# chickengate.net
KiCad netlist of a schematic drawn in EAGLE
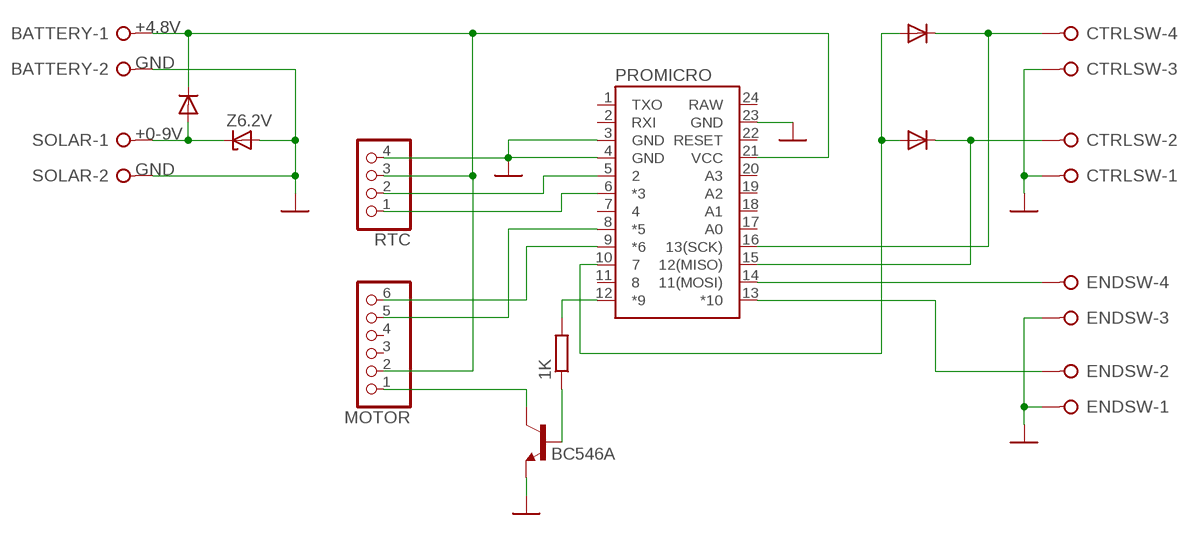
[diagram p0: schematic, sheet 1]

(export (version "E")
  (design (tool "Eeschema 10.0.6"))
  (components
    (comp (ref "1K")
      (value "R-EU_0207/12")
      (footprint "eagle-import:0207_12")
      (libsource (lib "eagle-import") (part "R-EU_0207/12"))
    )
    (comp (ref "BATTERY")
      (value "W237-02P")
      (footprint "eagle-import:W237-132")
      (libsource (lib "eagle-import") (part "W237-02P"))
    )
    (comp (ref "CTRLSW")
      (value "W237-04P")
      (footprint "eagle-import:W237-4P")
      (libsource (lib "eagle-import") (part "W237-04P"))
    )
    (comp (ref "D1")
      (value "1N4004")
      (footprint "eagle-import:DO41-10")
      (libsource (lib "eagle-import") (part "1N4004"))
    )
    (comp (ref "D2")
      (value "1N4004")
      (footprint "eagle-import:DO41-10")
      (libsource (lib "eagle-import") (part "1N4004"))
    )
    (comp (ref "D3")
      (value "1N4004")
      (footprint "eagle-import:DO41-10")
      (libsource (lib "eagle-import") (part "1N4004"))
    )
    (comp (ref "ENDSW")
      (value "W237-04P")
      (footprint "eagle-import:W237-4P")
      (libsource (lib "eagle-import") (part "W237-04P"))
    )
    (comp (ref "MOTOR")
      (value "PINHD-1X6")
      (footprint "eagle-import:1X06")
      (libsource (lib "eagle-import") (part "PINHD-1X6"))
    )
    (comp (ref "PROMICRO")
      (value "SPARKFUN_PRO_MICRO")
      (footprint "eagle-import:SPARKFUN_PRO_MICRO")
      (libsource (lib "eagle-import") (part "SPARKFUN_PRO_MICRO"))
    )
    (comp (ref "Q1")
      (value "BC546A")
      (footprint "eagle-import:TO92-EBC")
      (libsource (lib "eagle-import") (part "BC546A"))
    )
    (comp (ref "RTC")
      (value "PINHD-1X4")
      (footprint "eagle-import:1X04")
      (libsource (lib "eagle-import") (part "PINHD-1X4"))
    )
    (comp (ref "SOLAR")
      (value "W237-02P")
      (footprint "eagle-import:W237-132")
      (libsource (lib "eagle-import") (part "W237-02P"))
    )
    (comp (ref "Z6.2V")
      (value "ZPD")
      (footprint "eagle-import:DO35Z10")
      (libsource (lib "eagle-import") (part "ZPD"))
    )
  )
  (nets
    (net (code "1") (name "/+0-9V") (class "Default")
      (node (ref "D1") (pin "A") (pinfunction "A_A") (pintype "passive"))
      (node (ref "SOLAR") (pin "1") (pinfunction "KL_1") (pintype "passive"))
      (node (ref "Z6.2V") (pin "C") (pinfunction "C_C") (pintype "passive"))
    )
    (net (code "2") (name "/+4.8V") (class "Default")
      (node (ref "BATTERY") (pin "1") (pinfunction "KL_1") (pintype "passive"))
      (node (ref "D1") (pin "C") (pinfunction "C_C") (pintype "passive"))
      (node (ref "MOTOR") (pin "2") (pinfunction "2_2") (pintype "passive"))
      (node (ref "PROMICRO") (pin "21") (pinfunction "VCC_21") (pintype "power_in"))
      (node (ref "RTC") (pin "3") (pinfunction "3_3") (pintype "passive"))
    )
    (net (code "3") (name "/RAW") (class "Default")
      (node (ref "PROMICRO") (pin "24") (pinfunction "RAW_24") (pintype "power_in"))
    )
    (net (code "4") (name "GND") (class "Default")
      (node (ref "BATTERY") (pin "2") (pinfunction "KL_2") (pintype "passive"))
      (node (ref "CTRLSW") (pin "1") (pinfunction "KL_1") (pintype "passive"))
      (node (ref "CTRLSW") (pin "3") (pinfunction "KL_3") (pintype "passive"))
      (node (ref "ENDSW") (pin "1") (pinfunction "KL_1") (pintype "passive"))
      (node (ref "ENDSW") (pin "3") (pinfunction "KL_3") (pintype "passive"))
      (node (ref "PROMICRO") (pin "23") (pinfunction "GND_23") (pintype "power_in"))
      (node (ref "PROMICRO") (pin "3") (pinfunction "GND_3") (pintype "power_in"))
      (node (ref "PROMICRO") (pin "4") (pinfunction "GND_4") (pintype "power_in"))
      (node (ref "Q1") (pin "E") (pinfunction "E_E") (pintype "passive"))
      (node (ref "RTC") (pin "4") (pinfunction "4_4") (pintype "passive"))
      (node (ref "SOLAR") (pin "2") (pinfunction "KL_2") (pintype "passive"))
      (node (ref "Z6.2V") (pin "A") (pinfunction "A_A") (pintype "passive"))
    )
    (net (code "5") (name "Net-(1K-Pad1)") (class "Default")
      (node (ref "1K") (pin "1") (pinfunction "1_1") (pintype "passive"))
      (node (ref "Q1") (pin "B") (pinfunction "B_B") (pintype "passive"))
    )
    (net (code "6") (name "Net-(CTRLSWB-KL)") (class "Default")
      (node (ref "CTRLSW") (pin "2") (pinfunction "KL_2") (pintype "passive"))
      (node (ref "D3") (pin "C") (pinfunction "C_C") (pintype "passive"))
      (node (ref "PROMICRO") (pin "15") (pinfunction "12(MISO)_15") (pintype "bidirectional"))
    )
    (net (code "7") (name "Net-(CTRLSWD-KL)") (class "Default")
      (node (ref "CTRLSW") (pin "4") (pinfunction "KL_4") (pintype "passive"))
      (node (ref "D2") (pin "C") (pinfunction "C_C") (pintype "passive"))
      (node (ref "PROMICRO") (pin "16") (pinfunction "13(SCK)_16") (pintype "bidirectional"))
    )
    (net (code "8") (name "Net-(ENDSWB-KL)") (class "Default")
      (node (ref "ENDSW") (pin "2") (pinfunction "KL_2") (pintype "passive"))
      (node (ref "PROMICRO") (pin "13") (pinfunction "*10_13") (pintype "bidirectional"))
    )
    (net (code "9") (name "Net-(ENDSWD-KL)") (class "Default")
      (node (ref "ENDSW") (pin "4") (pinfunction "KL_4") (pintype "passive"))
      (node (ref "PROMICRO") (pin "14") (pinfunction "11(MOSI)_14") (pintype "bidirectional"))
    )
    (net (code "10") (name "Net-(MOTOR-Pad1)") (class "Default")
      (node (ref "MOTOR") (pin "1") (pinfunction "1_1") (pintype "passive"))
      (node (ref "Q1") (pin "C") (pinfunction "C_C") (pintype "passive"))
    )
    (net (code "11") (name "Net-(PROMICRO-*3)") (class "Default")
      (node (ref "PROMICRO") (pin "6") (pinfunction "*3_6") (pintype "bidirectional"))
      (node (ref "RTC") (pin "1") (pinfunction "1_1") (pintype "passive"))
    )
    (net (code "12") (name "Net-(PROMICRO-*5)") (class "Default")
      (node (ref "MOTOR") (pin "5") (pinfunction "5_5") (pintype "passive"))
      (node (ref "PROMICRO") (pin "8") (pinfunction "*5_8") (pintype "bidirectional"))
    )
    (net (code "13") (name "Net-(PROMICRO-*6)") (class "Default")
      (node (ref "MOTOR") (pin "6") (pinfunction "6_6") (pintype "passive"))
      (node (ref "PROMICRO") (pin "9") (pinfunction "*6_9") (pintype "bidirectional"))
    )
    (net (code "14") (name "Net-(PROMICRO-*9)") (class "Default")
      (node (ref "1K") (pin "2") (pinfunction "2_2") (pintype "passive"))
      (node (ref "PROMICRO") (pin "12") (pinfunction "*9_12") (pintype "bidirectional"))
    )
    (net (code "15") (name "Net-(PROMICRO-2)") (class "Default")
      (node (ref "PROMICRO") (pin "5") (pinfunction "2_5") (pintype "bidirectional"))
      (node (ref "RTC") (pin "2") (pinfunction "2_2") (pintype "passive"))
    )
    (net (code "16") (name "Net-(PROMICRO-7)") (class "Default")
      (node (ref "D2") (pin "A") (pinfunction "A_A") (pintype "passive"))
      (node (ref "D3") (pin "A") (pinfunction "A_A") (pintype "passive"))
      (node (ref "PROMICRO") (pin "10") (pinfunction "7_10") (pintype "bidirectional"))
    )
    (net (code "17") (name "unconnected-(MOTOR-Pad3)") (class "Default")
      (node (ref "MOTOR") (pin "3") (pinfunction "3_3") (pintype "passive"))
    )
    (net (code "18") (name "unconnected-(MOTOR-Pad4)") (class "Default")
      (node (ref "MOTOR") (pin "4") (pinfunction "4_4") (pintype "passive"))
    )
    (net (code "19") (name "unconnected-(PROMICRO-4-Pad7)") (class "Default")
      (node (ref "PROMICRO") (pin "7") (pinfunction "4_7") (pintype "bidirectional"))
    )
    (net (code "20") (name "unconnected-(PROMICRO-8-Pad11)") (class "Default")
      (node (ref "PROMICRO") (pin "11") (pinfunction "8_11") (pintype "bidirectional"))
    )
    (net (code "21") (name "unconnected-(PROMICRO-A0-Pad17)") (class "Default")
      (node (ref "PROMICRO") (pin "17") (pinfunction "A0_17") (pintype "bidirectional"))
    )
    (net (code "22") (name "unconnected-(PROMICRO-A1-Pad18)") (class "Default")
      (node (ref "PROMICRO") (pin "18") (pinfunction "A1_18") (pintype "bidirectional"))
    )
    (net (code "23") (name "unconnected-(PROMICRO-A2-Pad19)") (class "Default")
      (node (ref "PROMICRO") (pin "19") (pinfunction "A2_19") (pintype "bidirectional"))
    )
    (net (code "24") (name "unconnected-(PROMICRO-A3-Pad20)") (class "Default")
      (node (ref "PROMICRO") (pin "20") (pinfunction "A3_20") (pintype "bidirectional"))
    )
    (net (code "25") (name "unconnected-(PROMICRO-RESET-Pad22)") (class "Default")
      (node (ref "PROMICRO") (pin "22") (pinfunction "RESET_22") (pintype "bidirectional"))
    )
    (net (code "26") (name "unconnected-(PROMICRO-RXI-Pad2)") (class "Default")
      (node (ref "PROMICRO") (pin "2") (pinfunction "RXI_2") (pintype "bidirectional"))
    )
    (net (code "27") (name "unconnected-(PROMICRO-TXO-Pad1)") (class "Default")
      (node (ref "PROMICRO") (pin "1") (pinfunction "TXO_1") (pintype "bidirectional"))
    )
  )
)
